# GR_Action.net
KiCad netlist of a schematic drawn in Altium Designer
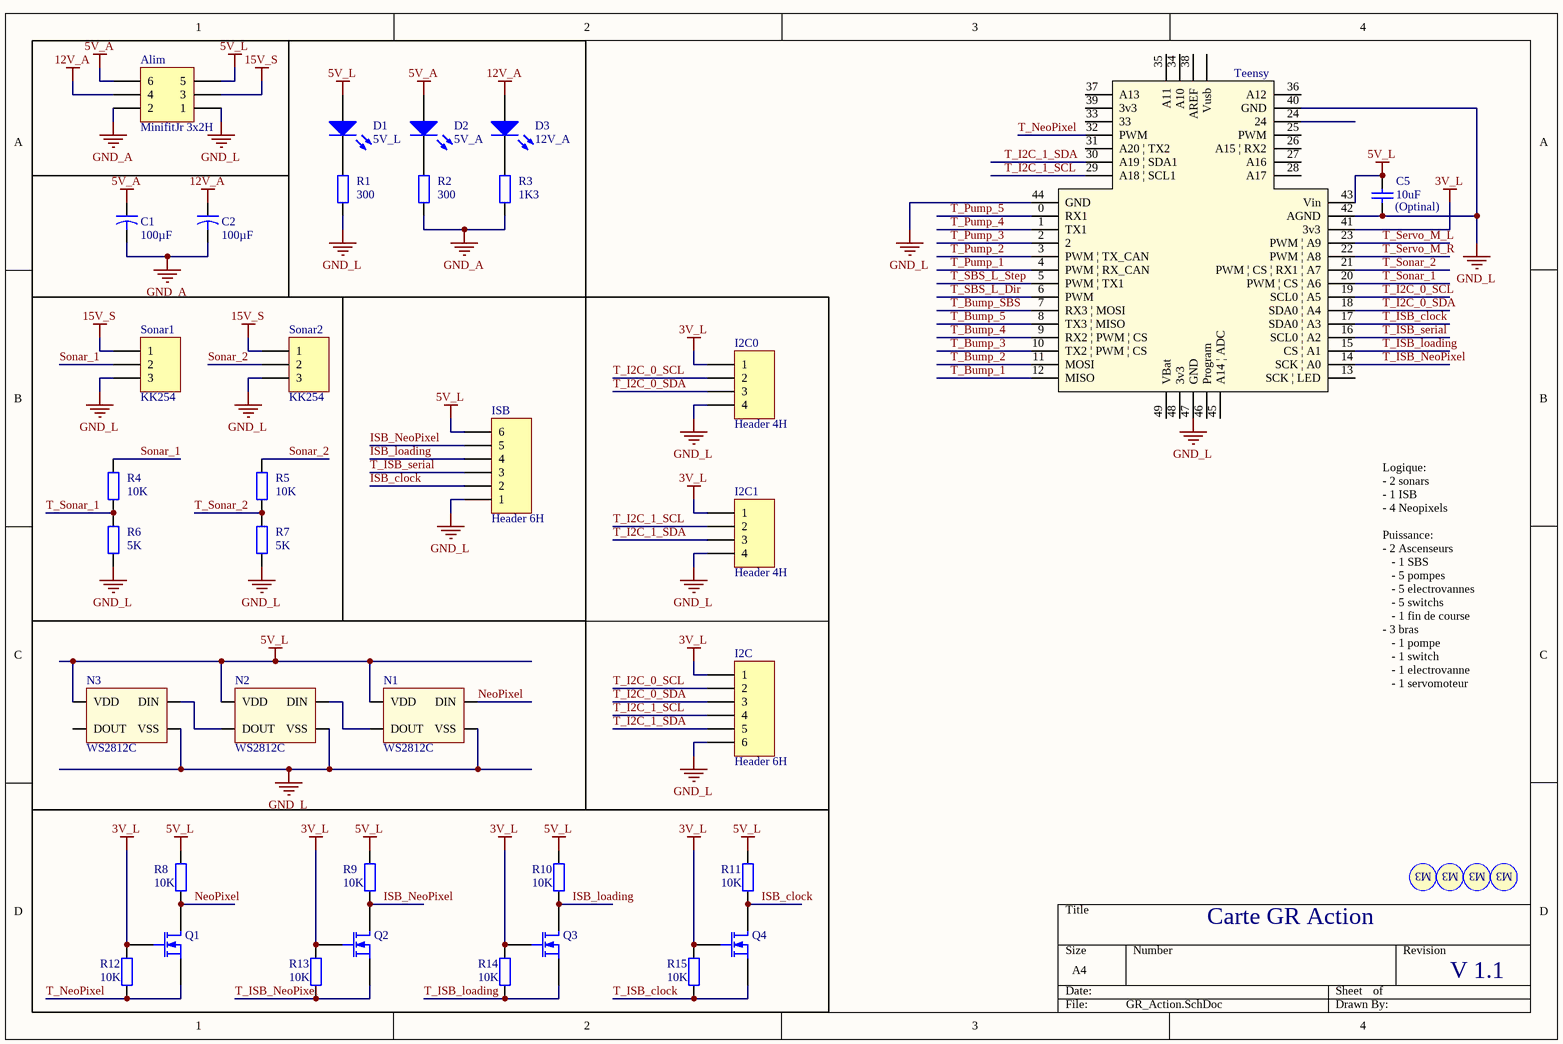
[diagram p0: GR_Action.SchDoc]

(export (version "E")
  (design (tool "Eeschema 10.0.6"))
  (components
    (comp (ref "Alim")
      (value "MinifitJr 3x2H")
      (footprint "MOLEX_MINIFITJR_3X2")
      (description "Header, 3-Pin, Dual row, Right Angle")
      (fields (field (name "PUBLISHER") "Altium Limited"))
      (libsource (lib "Miscellaneous Connectors") (part "Header 3X2H"))
    )
    (comp (ref "C1")
      (value "100µF")
      (footprint "Condensateur")
      (description "Capacitor")
      (fields (field (name "Comment") "Cap2") (field (name "PUBLISHER") "Altium Limited"))
      (libsource (lib "Miscellaneous Devices") (part "Cap2"))
    )
    (comp (ref "C2")
      (value "100µF")
      (footprint "Condensateur")
      (description "Capacitor")
      (fields (field (name "Comment") "Cap2") (field (name "PUBLISHER") "Altium Limited"))
      (libsource (lib "Miscellaneous Devices") (part "Cap2"))
    )
    (comp (ref "C5")
      (value "(Optinal)")
      (footprint "Capacitor 1206")
      (description "Capacitor")
      (fields (field (name "ALTIUM_VALUE") "10uF") (field (name "PUBLISHER") "Altium Limited"))
      (libsource (lib "Miscellaneous Devices") (part "Cap"))
    )
    (comp (ref "D1")
      (value "5V_L")
      (footprint "KP-3216SEC")
      (description "Typical RED, GREEN, YELLOW, AMBER GaAs LED")
      (fields (field (name "PUBLISHER") "Altium Limited"))
      (libsource (lib "Miscellaneous Devices") (part "LED2"))
    )
    (comp (ref "D2")
      (value "5V_A")
      (footprint "KP-3216SEC")
      (description "Typical RED, GREEN, YELLOW, AMBER GaAs LED")
      (fields (field (name "PUBLISHER") "Altium Limited"))
      (libsource (lib "Miscellaneous Devices") (part "LED2"))
    )
    (comp (ref "D3")
      (value "12V_A")
      (footprint "KP-3216SEC")
      (description "Typical RED, GREEN, YELLOW, AMBER GaAs LED")
      (fields (field (name "PUBLISHER") "Altium Limited"))
      (libsource (lib "Miscellaneous Devices") (part "LED2"))
    )
    (comp (ref "I2C")
      (value "Header 6H")
      (footprint "S6B-XH-A")
      (description "Header, 6-Pin, Right Angle")
      (fields (field (name "PUBLISHER") "Altium Limited"))
      (libsource (lib "") (part "Header 6H_1"))
    )
    (comp (ref "I2C0")
      (value "Header 4H")
      (footprint "S4B-XH-A")
      (description "Header, 4-Pin, Right Angle")
      (fields (field (name "PUBLISHER") "Altium Limited"))
      (libsource (lib "Miscellaneous Connectors") (part "Header 4H"))
    )
    (comp (ref "I2C1")
      (value "Header 4H")
      (footprint "S4B-XH-A")
      (description "Header, 4-Pin, Right Angle")
      (fields (field (name "PUBLISHER") "Altium Limited"))
      (libsource (lib "Miscellaneous Connectors") (part "Header 4H"))
    )
    (comp (ref "ISB")
      (value "Header 6H")
      (footprint "S6B-XH-A")
      (description "Header, 6-Pin, Right Angle")
      (fields (field (name "PUBLISHER") "Altium Limited"))
      (libsource (lib "Miscellaneous Connectors") (part "Header 6H"))
    )
    (comp (ref "N1")
      (value "WS2812C")
      (footprint "WS2812C")
      (description "Intelligent control LED")
      (libsource (lib "Robot_2020") (part "WS2812C"))
    )
    (comp (ref "N2")
      (value "WS2812C")
      (footprint "WS2812C")
      (description "Intelligent control LED")
      (libsource (lib "Robot_2020") (part "WS2812C"))
    )
    (comp (ref "N3")
      (value "WS2812C")
      (footprint "WS2812C")
      (description "Intelligent control LED")
      (libsource (lib "Robot_2020") (part "WS2812C"))
    )
    (comp (ref "Q1")
      (value "MOSFET-N")
      (footprint "SOT23_M")
      (description "N-Channel MOSFET")
      (fields (field (name "PUBLISHER") "Altium Limited"))
      (libsource (lib "Miscellaneous Devices") (part "MOSFET-N"))
    )
    (comp (ref "Q2")
      (value "MOSFET-N")
      (footprint "SOT23_M")
      (description "N-Channel MOSFET")
      (fields (field (name "PUBLISHER") "Altium Limited"))
      (libsource (lib "Miscellaneous Devices") (part "MOSFET-N"))
    )
    (comp (ref "Q3")
      (value "MOSFET-N")
      (footprint "SOT23_M")
      (description "N-Channel MOSFET")
      (fields (field (name "PUBLISHER") "Altium Limited"))
      (libsource (lib "Miscellaneous Devices") (part "MOSFET-N"))
    )
    (comp (ref "Q4")
      (value "MOSFET-N")
      (footprint "SOT23_M")
      (description "N-Channel MOSFET")
      (fields (field (name "PUBLISHER") "Altium Limited"))
      (libsource (lib "Miscellaneous Devices") (part "MOSFET-N"))
    )
    (comp (ref "R1")
      (value "300")
      (footprint "Resistor 1206")
      (description "Resistor")
      (fields (field (name "Comment") "Res2") (field (name "PUBLISHER") "Altium Limited"))
      (libsource (lib "Miscellaneous Devices") (part "Res2"))
    )
    (comp (ref "R2")
      (value "300")
      (footprint "Resistor 1206")
      (description "Resistor")
      (fields (field (name "Comment") "Res2") (field (name "PUBLISHER") "Altium Limited"))
      (libsource (lib "") (part "Res2_1"))
    )
    (comp (ref "R3")
      (value "1K3")
      (footprint "Resistor 1206")
      (description "Resistor")
      (fields (field (name "Comment") "Res2") (field (name "PUBLISHER") "Altium Limited"))
      (libsource (lib "") (part "Res2_1"))
    )
    (comp (ref "R4")
      (value "10K")
      (footprint "Resistor 1206")
      (description "Resistor")
      (fields (field (name "Comment") "Res2") (field (name "PUBLISHER") "Altium Limited"))
      (libsource (lib "") (part "Res2_1"))
    )
    (comp (ref "R5")
      (value "10K")
      (footprint "Resistor 1206")
      (description "Resistor")
      (fields (field (name "Comment") "Res2") (field (name "PUBLISHER") "Altium Limited"))
      (libsource (lib "") (part "Res2_1"))
    )
    (comp (ref "R6")
      (value "5K")
      (footprint "Resistor 1206")
      (description "Resistor")
      (fields (field (name "Comment") "Res2") (field (name "PUBLISHER") "Altium Limited"))
      (libsource (lib "") (part "Res2_1"))
    )
    (comp (ref "R7")
      (value "5K")
      (footprint "Resistor 1206")
      (description "Resistor")
      (fields (field (name "Comment") "Res2") (field (name "PUBLISHER") "Altium Limited"))
      (libsource (lib "") (part "Res2_1"))
    )
    (comp (ref "R8")
      (value "10K")
      (footprint "Resistor 1206")
      (description "Resistor")
      (fields (field (name "Comment") "Res2") (field (name "PUBLISHER") "Altium Limited"))
      (libsource (lib "Miscellaneous Devices") (part "Res2"))
    )
    (comp (ref "R9")
      (value "10K")
      (footprint "Resistor 1206")
      (description "Resistor")
      (fields (field (name "Comment") "Res2") (field (name "PUBLISHER") "Altium Limited"))
      (libsource (lib "Miscellaneous Devices") (part "Res2"))
    )
    (comp (ref "R10")
      (value "10K")
      (footprint "Resistor 1206")
      (description "Resistor")
      (fields (field (name "Comment") "Res2") (field (name "PUBLISHER") "Altium Limited"))
      (libsource (lib "Miscellaneous Devices") (part "Res2"))
    )
    (comp (ref "R11")
      (value "10K")
      (footprint "Resistor 1206")
      (description "Resistor")
      (fields (field (name "Comment") "Res2") (field (name "PUBLISHER") "Altium Limited"))
      (libsource (lib "Miscellaneous Devices") (part "Res2"))
    )
    (comp (ref "R12")
      (value "10K")
      (footprint "Resistor 1206")
      (description "Resistor")
      (fields (field (name "Comment") "Res2") (field (name "PUBLISHER") "Altium Limited"))
      (libsource (lib "Miscellaneous Devices") (part "Res2"))
    )
    (comp (ref "R13")
      (value "10K")
      (footprint "Resistor 1206")
      (description "Resistor")
      (fields (field (name "Comment") "Res2") (field (name "PUBLISHER") "Altium Limited"))
      (libsource (lib "Miscellaneous Devices") (part "Res2"))
    )
    (comp (ref "R14")
      (value "10K")
      (footprint "Resistor 1206")
      (description "Resistor")
      (fields (field (name "Comment") "Res2") (field (name "PUBLISHER") "Altium Limited"))
      (libsource (lib "Miscellaneous Devices") (part "Res2"))
    )
    (comp (ref "R15")
      (value "10K")
      (footprint "Resistor 1206")
      (description "Resistor")
      (fields (field (name "Comment") "Res2") (field (name "PUBLISHER") "Altium Limited"))
      (libsource (lib "Miscellaneous Devices") (part "Res2"))
    )
    (comp (ref "S1")
      (value "Screw M3")
      (footprint "Screw M3")
      (libsource (lib "Robot_2020") (part "Screw M3"))
    )
    (comp (ref "S2")
      (value "Screw M3")
      (footprint "Screw M3")
      (libsource (lib "Robot_2020") (part "Screw M3"))
    )
    (comp (ref "S3")
      (value "Screw M3")
      (footprint "Screw M3")
      (libsource (lib "Robot_2020") (part "Screw M3"))
    )
    (comp (ref "S4")
      (value "Screw M3")
      (footprint "Screw M3")
      (libsource (lib "Robot_2020") (part "Screw M3"))
    )
    (comp (ref "Sonar1")
      (value "KK254")
      (footprint "MOLEX KK254 3X1H M")
      (description "Header, 3-Pin, Right Angle")
      (fields (field (name "PUBLISHER") "Altium Limited"))
      (libsource (lib "Miscellaneous Connectors") (part "Header 3H"))
    )
    (comp (ref "Sonar2")
      (value "KK254")
      (footprint "MOLEX KK254 3X1H M")
      (description "Header, 3-Pin, Right Angle")
      (fields (field (name "PUBLISHER") "Altium Limited"))
      (libsource (lib "Miscellaneous Connectors") (part "Header 3H"))
    )
    (comp (ref "Teensy")
      (value "Teensy 3.2")
      (footprint "teensy")
      (libsource (lib "Robot_2020") (part "teensy3.2"))
    )
  )
  (nets
    (net (code "1") (name "/ISB_NeoPixel") (class "Default")
      (node (ref "ISB") (pin "5") (pinfunction "5_5") (pintype "passive"))
      (node (ref "Q2") (pin "1") (pinfunction "D_1") (pintype "passive"))
      (node (ref "R9") (pin "1") (pinfunction "1_1") (pintype "passive"))
    )
    (net (code "2") (name "/ISB_clock") (class "Default")
      (node (ref "ISB") (pin "2") (pinfunction "2_2") (pintype "passive"))
      (node (ref "Q4") (pin "1") (pinfunction "D_1") (pintype "passive"))
      (node (ref "R11") (pin "1") (pinfunction "1_1") (pintype "passive"))
    )
    (net (code "3") (name "/ISB_loading") (class "Default")
      (node (ref "ISB") (pin "4") (pinfunction "4_4") (pintype "passive"))
      (node (ref "Q3") (pin "1") (pinfunction "D_1") (pintype "passive"))
      (node (ref "R10") (pin "1") (pinfunction "1_1") (pintype "passive"))
    )
    (net (code "4") (name "/NeoPixel") (class "Default")
      (node (ref "N1") (pin "4") (pinfunction "DIN_4") (pintype "passive"))
      (node (ref "Q1") (pin "1") (pinfunction "D_1") (pintype "passive"))
      (node (ref "R8") (pin "1") (pinfunction "1_1") (pintype "passive"))
    )
    (net (code "5") (name "/Sonar_1") (class "Default")
      (node (ref "R4") (pin "1") (pinfunction "1_1") (pintype "passive"))
      (node (ref "Sonar1") (pin "2") (pinfunction "2_2") (pintype "passive"))
    )
    (net (code "6") (name "/Sonar_2") (class "Default")
      (node (ref "R5") (pin "1") (pinfunction "1_1") (pintype "passive"))
      (node (ref "Sonar2") (pin "2") (pinfunction "2_2") (pintype "passive"))
    )
    (net (code "7") (name "/T_Bump_1") (class "Default")
      (node (ref "Teensy") (pin "12") (pinfunction "MISO_12") (pintype "passive"))
    )
    (net (code "8") (name "/T_Bump_2") (class "Default")
      (node (ref "Teensy") (pin "11") (pinfunction "MOSI_11") (pintype "passive"))
    )
    (net (code "9") (name "/T_Bump_3") (class "Default")
      (node (ref "Teensy") (pin "10") (pinfunction "TX2_¦_PWM_¦_CS_10") (pintype "passive"))
    )
    (net (code "10") (name "/T_Bump_4") (class "Default")
      (node (ref "Teensy") (pin "9") (pinfunction "RX2_¦_PWM_¦_CS_9") (pintype "passive"))
    )
    (net (code "11") (name "/T_Bump_5") (class "Default")
      (node (ref "Teensy") (pin "8") (pinfunction "TX3_¦_MISO_8") (pintype "passive"))
    )
    (net (code "12") (name "/T_Bump_SBS") (class "Default")
      (node (ref "Teensy") (pin "7") (pinfunction "RX3_¦_MOSI_7") (pintype "passive"))
    )
    (net (code "13") (name "/T_I2C_0_SCL") (class "Default")
      (node (ref "I2C") (pin "2") (pinfunction "2_2") (pintype "passive"))
      (node (ref "I2C0") (pin "2") (pinfunction "2_2") (pintype "passive"))
      (node (ref "Teensy") (pin "19") (pinfunction "SCL0_¦_A5_19") (pintype "passive"))
    )
    (net (code "14") (name "/T_I2C_0_SDA") (class "Default")
      (node (ref "I2C") (pin "3") (pinfunction "3_3") (pintype "passive"))
      (node (ref "I2C0") (pin "3") (pinfunction "3_3") (pintype "passive"))
      (node (ref "Teensy") (pin "18") (pinfunction "SDA0_¦_A4_18") (pintype "passive"))
    )
    (net (code "15") (name "/T_I2C_1_SCL") (class "Default")
      (node (ref "I2C") (pin "4") (pinfunction "4_4") (pintype "passive"))
      (node (ref "I2C1") (pin "2") (pinfunction "2_2") (pintype "passive"))
      (node (ref "Teensy") (pin "29") (pinfunction "A18_¦_SCL1_29") (pintype "passive"))
    )
    (net (code "16") (name "/T_I2C_1_SDA") (class "Default")
      (node (ref "I2C") (pin "5") (pinfunction "5_5") (pintype "passive"))
      (node (ref "I2C1") (pin "3") (pinfunction "3_3") (pintype "passive"))
      (node (ref "Teensy") (pin "30") (pinfunction "A19_¦_SDA1_30") (pintype "passive"))
    )
    (net (code "17") (name "/T_ISB_NeoPixel") (class "Default")
      (node (ref "Q2") (pin "3") (pinfunction "S_3") (pintype "passive"))
      (node (ref "R13") (pin "1") (pinfunction "1_1") (pintype "passive"))
      (node (ref "Teensy") (pin "14") (pinfunction "SCK_¦_A0_14") (pintype "passive"))
    )
    (net (code "18") (name "/T_ISB_clock") (class "Default")
      (node (ref "Q4") (pin "3") (pinfunction "S_3") (pintype "passive"))
      (node (ref "R15") (pin "1") (pinfunction "1_1") (pintype "passive"))
      (node (ref "Teensy") (pin "17") (pinfunction "SDA0_¦_A3_17") (pintype "passive"))
    )
    (net (code "19") (name "/T_ISB_loading") (class "Default")
      (node (ref "Q3") (pin "3") (pinfunction "S_3") (pintype "passive"))
      (node (ref "R14") (pin "1") (pinfunction "1_1") (pintype "passive"))
      (node (ref "Teensy") (pin "15") (pinfunction "CS_¦_A1_15") (pintype "passive"))
    )
    (net (code "20") (name "/T_ISB_serial") (class "Default")
      (node (ref "ISB") (pin "3") (pinfunction "3_3") (pintype "passive"))
      (node (ref "Teensy") (pin "16") (pinfunction "SCL0_¦_A2_16") (pintype "passive"))
    )
    (net (code "21") (name "/T_NeoPixel") (class "Default")
      (node (ref "Q1") (pin "3") (pinfunction "S_3") (pintype "passive"))
      (node (ref "R12") (pin "1") (pinfunction "1_1") (pintype "passive"))
      (node (ref "Teensy") (pin "32") (pinfunction "PWM_32") (pintype "passive"))
    )
    (net (code "22") (name "/T_Pump_1") (class "Default")
      (node (ref "Teensy") (pin "4") (pinfunction "PWM_¦_RX_CAN_4") (pintype "passive"))
    )
    (net (code "23") (name "/T_Pump_2") (class "Default")
      (node (ref "Teensy") (pin "3") (pinfunction "PWM_¦_TX_CAN_3") (pintype "passive"))
    )
    (net (code "24") (name "/T_Pump_3") (class "Default")
      (node (ref "Teensy") (pin "2") (pinfunction "2_2") (pintype "passive"))
    )
    (net (code "25") (name "/T_Pump_4") (class "Default")
      (node (ref "Teensy") (pin "1") (pinfunction "TX1_1") (pintype "passive"))
    )
    (net (code "26") (name "/T_Pump_5") (class "Default")
      (node (ref "Teensy") (pin "0") (pinfunction "RX1_0") (pintype "passive"))
    )
    (net (code "27") (name "/T_SBS_L_Dir") (class "Default")
      (node (ref "Teensy") (pin "6") (pinfunction "PWM_6") (pintype "passive"))
    )
    (net (code "28") (name "/T_SBS_L_Step") (class "Default")
      (node (ref "Teensy") (pin "5") (pinfunction "PWM_¦_TX1_5") (pintype "passive"))
    )
    (net (code "29") (name "/T_Servo_M_L") (class "Default")
      (node (ref "Teensy") (pin "23") (pinfunction "PWM_¦_A9_23") (pintype "passive"))
    )
    (net (code "30") (name "/T_Servo_M_R") (class "Default")
      (node (ref "Teensy") (pin "22") (pinfunction "PWM_¦_A8_22") (pintype "passive"))
    )
    (net (code "31") (name "/T_Sonar_1") (class "Default")
      (node (ref "R4") (pin "2") (pinfunction "2_2") (pintype "passive"))
      (node (ref "R6") (pin "1") (pinfunction "1_1") (pintype "passive"))
      (node (ref "Teensy") (pin "20") (pinfunction "PWM_¦_CS_¦_A6_20") (pintype "passive"))
    )
    (net (code "32") (name "/T_Sonar_2") (class "Default")
      (node (ref "R5") (pin "2") (pinfunction "2_2") (pintype "passive"))
      (node (ref "R7") (pin "1") (pinfunction "1_1") (pintype "passive"))
      (node (ref "Teensy") (pin "21") (pinfunction "PWM_¦_CS_¦_RX1_¦_A7_21") (pintype "passive"))
    )
    (net (code "33") (name "3V_L") (class "Default")
      (node (ref "I2C") (pin "1") (pinfunction "1_1") (pintype "passive"))
      (node (ref "I2C0") (pin "1") (pinfunction "1_1") (pintype "passive"))
      (node (ref "I2C1") (pin "1") (pinfunction "1_1") (pintype "passive"))
      (node (ref "Q1") (pin "2") (pinfunction "G_2") (pintype "passive"))
      (node (ref "Q2") (pin "2") (pinfunction "G_2") (pintype "passive"))
      (node (ref "Q3") (pin "2") (pinfunction "G_2") (pintype "passive"))
      (node (ref "Q4") (pin "2") (pinfunction "G_2") (pintype "passive"))
      (node (ref "R12") (pin "2") (pinfunction "2_2") (pintype "passive"))
      (node (ref "R13") (pin "2") (pinfunction "2_2") (pintype "passive"))
      (node (ref "R14") (pin "2") (pinfunction "2_2") (pintype "passive"))
      (node (ref "R15") (pin "2") (pinfunction "2_2") (pintype "passive"))
      (node (ref "Teensy") (pin "41") (pinfunction "3v3_41") (pintype "passive"))
    )
    (net (code "34") (name "5V_A") (class "Default")
      (node (ref "Alim") (pin "6") (pinfunction "6_6") (pintype "passive"))
      (node (ref "C1") (pin "1") (pinfunction "1_1") (pintype "passive"))
      (node (ref "D2") (pin "1") (pinfunction "A_1") (pintype "passive"))
    )
    (net (code "35") (name "5V_L") (class "Default")
      (node (ref "Alim") (pin "5") (pinfunction "5_5") (pintype "passive"))
      (node (ref "C5") (pin "2") (pinfunction "2_2") (pintype "passive"))
      (node (ref "D1") (pin "1") (pinfunction "A_1") (pintype "passive"))
      (node (ref "ISB") (pin "6") (pinfunction "6_6") (pintype "passive"))
      (node (ref "N1") (pin "1") (pinfunction "VDD_1") (pintype "passive"))
      (node (ref "N2") (pin "1") (pinfunction "VDD_1") (pintype "passive"))
      (node (ref "N3") (pin "1") (pinfunction "VDD_1") (pintype "passive"))
      (node (ref "R10") (pin "2") (pinfunction "2_2") (pintype "passive"))
      (node (ref "R11") (pin "2") (pinfunction "2_2") (pintype "passive"))
      (node (ref "R8") (pin "2") (pinfunction "2_2") (pintype "passive"))
      (node (ref "R9") (pin "2") (pinfunction "2_2") (pintype "passive"))
      (node (ref "Teensy") (pin "43") (pinfunction "Vin_43") (pintype "passive"))
    )
    (net (code "36") (name "12V_A") (class "Default")
      (node (ref "Alim") (pin "4") (pinfunction "4_4") (pintype "passive"))
      (node (ref "C2") (pin "1") (pinfunction "1_1") (pintype "passive"))
      (node (ref "D3") (pin "1") (pinfunction "A_1") (pintype "passive"))
    )
    (net (code "37") (name "15V_S") (class "Default")
      (node (ref "Alim") (pin "3") (pinfunction "3_3") (pintype "passive"))
      (node (ref "Sonar1") (pin "1") (pinfunction "1_1") (pintype "passive"))
      (node (ref "Sonar2") (pin "1") (pinfunction "1_1") (pintype "passive"))
    )
    (net (code "38") (name "GND_A") (class "Default")
      (node (ref "Alim") (pin "2") (pinfunction "2_2") (pintype "passive"))
      (node (ref "C1") (pin "2") (pinfunction "2_2") (pintype "passive"))
      (node (ref "C2") (pin "2") (pinfunction "2_2") (pintype "passive"))
      (node (ref "R2") (pin "2") (pinfunction "2_2") (pintype "passive"))
      (node (ref "R3") (pin "2") (pinfunction "2_2") (pintype "passive"))
    )
    (net (code "39") (name "GND_L") (class "Default")
      (node (ref "Alim") (pin "1") (pinfunction "1_1") (pintype "passive"))
      (node (ref "C5") (pin "1") (pinfunction "1_1") (pintype "passive"))
      (node (ref "I2C") (pin "6") (pinfunction "6_6") (pintype "passive"))
      (node (ref "I2C0") (pin "4") (pinfunction "4_4") (pintype "passive"))
      (node (ref "I2C1") (pin "4") (pinfunction "4_4") (pintype "passive"))
      (node (ref "ISB") (pin "1") (pinfunction "1_1") (pintype "passive"))
      (node (ref "N1") (pin "3") (pinfunction "VSS_3") (pintype "passive"))
      (node (ref "N2") (pin "3") (pinfunction "VSS_3") (pintype "passive"))
      (node (ref "N3") (pin "3") (pinfunction "VSS_3") (pintype "passive"))
      (node (ref "R1") (pin "1") (pinfunction "1_1") (pintype "passive"))
      (node (ref "R6") (pin "2") (pinfunction "2_2") (pintype "passive"))
      (node (ref "R7") (pin "2") (pinfunction "2_2") (pintype "passive"))
      (node (ref "Sonar1") (pin "3") (pinfunction "3_3") (pintype "passive"))
      (node (ref "Sonar2") (pin "3") (pinfunction "3_3") (pintype "passive"))
      (node (ref "Teensy") (pin "40") (pinfunction "GND_40") (pintype "passive"))
      (node (ref "Teensy") (pin "42") (pinfunction "AGND_42") (pintype "passive"))
      (node (ref "Teensy") (pin "44") (pinfunction "GND_44") (pintype "passive"))
      (node (ref "Teensy") (pin "47") (pinfunction "GND_47") (pintype "passive"))
    )
    (net (code "40") (name "Net-(D1-K)") (class "Default")
      (node (ref "D1") (pin "2") (pinfunction "K_2") (pintype "passive"))
      (node (ref "R1") (pin "2") (pinfunction "2_2") (pintype "passive"))
    )
    (net (code "41") (name "Net-(D2-K)") (class "Default")
      (node (ref "D2") (pin "2") (pinfunction "K_2") (pintype "passive"))
      (node (ref "R2") (pin "1") (pinfunction "1_1") (pintype "passive"))
    )
    (net (code "42") (name "Net-(D3-K)") (class "Default")
      (node (ref "D3") (pin "2") (pinfunction "K_2") (pintype "passive"))
      (node (ref "R3") (pin "1") (pinfunction "1_1") (pintype "passive"))
    )
    (net (code "43") (name "Net-(N1-DOUT)") (class "Default")
      (node (ref "N1") (pin "2") (pinfunction "DOUT_2") (pintype "passive"))
      (node (ref "N2") (pin "4") (pinfunction "DIN_4") (pintype "passive"))
    )
    (net (code "44") (name "Net-(N2-DOUT)") (class "Default")
      (node (ref "N2") (pin "2") (pinfunction "DOUT_2") (pintype "passive"))
      (node (ref "N3") (pin "4") (pinfunction "DIN_4") (pintype "passive"))
    )
    (net (code "45") (name "unconnected-(N3-DOUT-Pad2)") (class "Default")
      (node (ref "N3") (pin "2") (pinfunction "DOUT_2") (pintype "passive"))
    )
    (net (code "46") (name "unconnected-(Teensy-3v3-Pad39)") (class "Default")
      (node (ref "Teensy") (pin "39") (pinfunction "3v3_39") (pintype "passive"))
    )
    (net (code "47") (name "unconnected-(Teensy-3v3-Pad48)") (class "Default")
      (node (ref "Teensy") (pin "48") (pinfunction "3v3_48") (pintype "passive"))
    )
    (net (code "48") (name "unconnected-(Teensy-A10-Pad34)") (class "Default")
      (node (ref "Teensy") (pin "34") (pinfunction "A10_34") (pintype "passive"))
    )
    (net (code "49") (name "unconnected-(Teensy-A11-Pad35)") (class "Default")
      (node (ref "Teensy") (pin "35") (pinfunction "A11_35") (pintype "passive"))
    )
    (net (code "50") (name "unconnected-(Teensy-A12-Pad36)") (class "Default")
      (node (ref "Teensy") (pin "36") (pinfunction "A12_36") (pintype "passive"))
    )
    (net (code "51") (name "unconnected-(Teensy-A13-Pad37)") (class "Default")
      (node (ref "Teensy") (pin "37") (pinfunction "A13_37") (pintype "passive"))
    )
    (net (code "52") (name "unconnected-(Teensy-A14_¦_ADC-Pad45)") (class "Default")
      (node (ref "Teensy") (pin "45") (pinfunction "A14_¦_ADC_45") (pintype "passive"))
    )
    (net (code "53") (name "unconnected-(Teensy-A15_¦_RX2-Pad26)") (class "Default")
      (node (ref "Teensy") (pin "26") (pinfunction "A15_¦_RX2_26") (pintype "passive"))
    )
    (net (code "54") (name "unconnected-(Teensy-A16-Pad27)") (class "Default")
      (node (ref "Teensy") (pin "27") (pinfunction "A16_27") (pintype "passive"))
    )
    (net (code "55") (name "unconnected-(Teensy-A17-Pad28)") (class "Default")
      (node (ref "Teensy") (pin "28") (pinfunction "A17_28") (pintype "passive"))
    )
    (net (code "56") (name "unconnected-(Teensy-A20_¦_TX2-Pad31)") (class "Default")
      (node (ref "Teensy") (pin "31") (pinfunction "A20_¦_TX2_31") (pintype "passive"))
    )
    (net (code "57") (name "unconnected-(Teensy-AREF-Pad38)") (class "Default")
      (node (ref "Teensy") (pin "38") (pinfunction "AREF_38") (pintype "passive"))
    )
    (net (code "58") (name "unconnected-(Teensy-PWM-Pad25)") (class "Default")
      (node (ref "Teensy") (pin "25") (pinfunction "PWM_25") (pintype "passive"))
    )
    (net (code "59") (name "unconnected-(Teensy-Pad24)") (class "Default")
      (node (ref "Teensy") (pin "24") (pinfunction "24_24") (pintype "passive"))
    )
    (net (code "60") (name "unconnected-(Teensy-Pad33)") (class "Default")
      (node (ref "Teensy") (pin "33") (pinfunction "33_33") (pintype "passive"))
    )
    (net (code "61") (name "unconnected-(Teensy-Program-Pad46)") (class "Default")
      (node (ref "Teensy") (pin "46") (pinfunction "Program_46") (pintype "passive"))
    )
    (net (code "62") (name "unconnected-(Teensy-SCK_¦_LED-Pad13)") (class "Default")
      (node (ref "Teensy") (pin "13") (pinfunction "SCK_¦_LED_13") (pintype "passive"))
    )
    (net (code "63") (name "unconnected-(Teensy-VBat-Pad49)") (class "Default")
      (node (ref "Teensy") (pin "49") (pinfunction "VBat_49") (pintype "passive"))
    )
    (net (code "64") (name "unconnected-(Teensy-Vusb-Pad50)") (class "Default")
      (node (ref "Teensy") (pin "50") (pinfunction "Vusb_50") (pintype "passive"))
    )
  )
)
